# NRF24L01P.net
KiCad netlist of a schematic drawn in Altium Designer
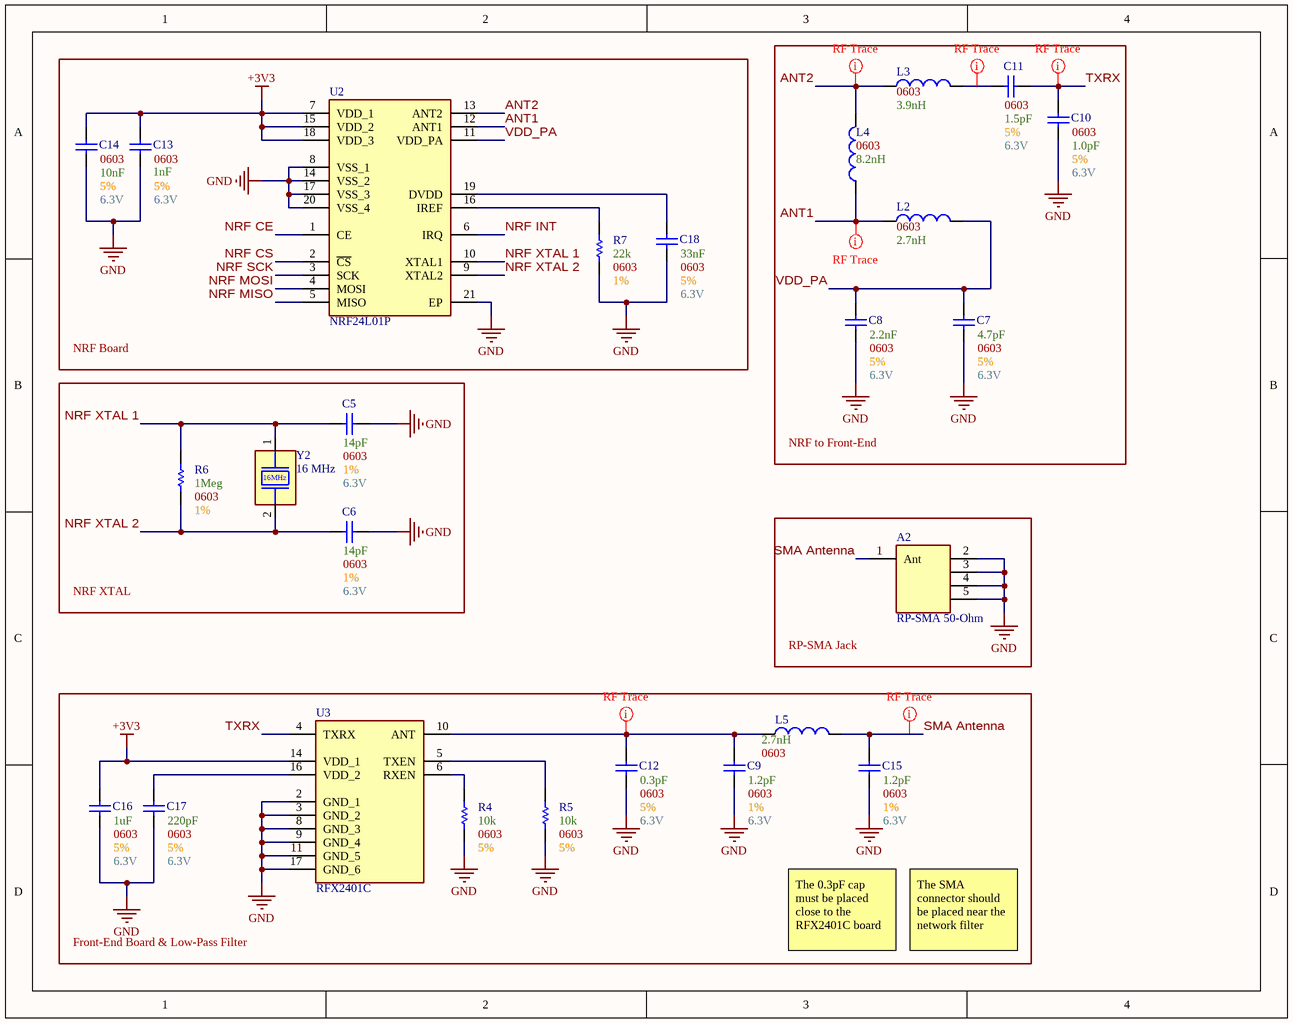
[diagram p0: NRF24L01P.SchDoc]

(export (version "E")
  (design (tool "Eeschema 10.0.6"))
  (components
    (comp (ref "A2")
      (value "RP-SMA 50-Ohm")
      (footprint "[SMA] RP-SMA 90deg Jack")
      (description "PCB.RPSMAFRA.HT")
      (libsource (lib "RADM Connectors") (part "[SMA] RP-SMA 90deg Jack"))
    )
    (comp (ref "C5")
      (value "SMD Nonpolarized")
      (footprint "[Cap] SMD 0603")
      (fields
        (field (name "TOLERANCE") "1%")
        (field (name "SIZE PACKAGE") "0603")
        (field (name "CAPACITANCE") "14pF")
        (field (name "VOLTAGE") "6.3V")
      )
      (libsource (lib "RADM Components") (part "[Cap] SMD Nonpolarized"))
    )
    (comp (ref "C6")
      (value "SMD Nonpolarized")
      (footprint "[Cap] SMD 0603")
      (fields
        (field (name "TOLERANCE") "1%")
        (field (name "SIZE PACKAGE") "0603")
        (field (name "CAPACITANCE") "14pF")
        (field (name "VOLTAGE") "6.3V")
      )
      (libsource (lib "RADM Components") (part "[Cap] SMD Nonpolarized"))
    )
    (comp (ref "C7")
      (value "SMD Nonpolarized")
      (footprint "[Cap] SMD 0603")
      (fields
        (field (name "TOLERANCE") "5%")
        (field (name "SIZE PACKAGE") "0603")
        (field (name "CAPACITANCE") "4.7pF")
        (field (name "VOLTAGE") "6.3V")
      )
      (libsource (lib "RADM Components") (part "[Cap] SMD Nonpolarized"))
    )
    (comp (ref "C8")
      (value "SMD Nonpolarized")
      (footprint "[Cap] SMD 0603")
      (fields
        (field (name "TOLERANCE") "5%")
        (field (name "SIZE PACKAGE") "0603")
        (field (name "CAPACITANCE") "2.2nF")
        (field (name "VOLTAGE") "6.3V")
      )
      (libsource (lib "RADM Components") (part "[Cap] SMD Nonpolarized"))
    )
    (comp (ref "C9")
      (value "SMD Nonpolarized")
      (footprint "[Cap] SMD 0603")
      (fields
        (field (name "VOLTAGE") "6.3V")
        (field (name "TOLERANCE") "1%")
        (field (name "SIZE PACKAGE") "0603")
        (field (name "CAPACITANCE") "1.2pF")
      )
      (libsource (lib "RADM Components") (part "[Cap] SMD Nonpolarized"))
    )
    (comp (ref "C10")
      (value "SMD Nonpolarized")
      (footprint "[Cap] SMD 0603")
      (fields
        (field (name "TOLERANCE") "5%")
        (field (name "SIZE PACKAGE") "0603")
        (field (name "CAPACITANCE") "1.0pF")
        (field (name "VOLTAGE") "6.3V")
      )
      (libsource (lib "RADM Components") (part "[Cap] SMD Nonpolarized"))
    )
    (comp (ref "C11")
      (value "SMD Nonpolarized")
      (footprint "[Cap] SMD 0603")
      (fields
        (field (name "TOLERANCE") "5%")
        (field (name "SIZE PACKAGE") "0603")
        (field (name "CAPACITANCE") "1.5pF")
        (field (name "VOLTAGE") "6.3V")
      )
      (libsource (lib "RADM Components") (part "[Cap] SMD Nonpolarized"))
    )
    (comp (ref "C12")
      (value "SMD Nonpolarized")
      (footprint "[Cap] SMD 0603")
      (fields
        (field (name "TOLERANCE") "5%")
        (field (name "SIZE PACKAGE") "0603")
        (field (name "CAPACITANCE") "0.3pF")
        (field (name "VOLTAGE") "6.3V")
      )
      (libsource (lib "RADM Components") (part "[Cap] SMD Nonpolarized"))
    )
    (comp (ref "C13")
      (value "SMD Nonpolarized")
      (footprint "[Cap] SMD 0603")
      (fields
        (field (name "TOLERANCE") "5%")
        (field (name "SIZE PACKAGE") "0603")
        (field (name "CAPACITANCE") "1nF")
        (field (name "VOLTAGE") "6.3V")
      )
      (libsource (lib "RADM Components") (part "[Cap] SMD Nonpolarized"))
    )
    (comp (ref "C14")
      (value "SMD Nonpolarized")
      (footprint "[Cap] SMD 0603")
      (fields
        (field (name "TOLERANCE") "5%")
        (field (name "SIZE PACKAGE") "0603")
        (field (name "CAPACITANCE") "10nF")
        (field (name "VOLTAGE") "6.3V")
      )
      (libsource (lib "RADM Components") (part "[Cap] SMD Nonpolarized"))
    )
    (comp (ref "C15")
      (value "SMD Nonpolarized")
      (footprint "[Cap] SMD 0603")
      (fields
        (field (name "VOLTAGE") "6.3V")
        (field (name "TOLERANCE") "1%")
        (field (name "SIZE PACKAGE") "0603")
        (field (name "CAPACITANCE") "1.2pF")
      )
      (libsource (lib "RADM Components") (part "[Cap] SMD Nonpolarized"))
    )
    (comp (ref "C16")
      (value "SMD Nonpolarized")
      (footprint "[Cap] SMD 0603")
      (fields
        (field (name "TOLERANCE") "5%")
        (field (name "SIZE PACKAGE") "0603")
        (field (name "CAPACITANCE") "1uF")
        (field (name "VOLTAGE") "6.3V")
      )
      (libsource (lib "RADM Components") (part "[Cap] SMD Nonpolarized"))
    )
    (comp (ref "C17")
      (value "SMD Nonpolarized")
      (footprint "[Cap] SMD 0603")
      (fields
        (field (name "TOLERANCE") "5%")
        (field (name "SIZE PACKAGE") "0603")
        (field (name "CAPACITANCE") "220pF")
        (field (name "VOLTAGE") "6.3V")
      )
      (libsource (lib "RADM Components") (part "[Cap] SMD Nonpolarized"))
    )
    (comp (ref "C18")
      (value "SMD Nonpolarized")
      (footprint "[Cap] SMD 0603")
      (fields
        (field (name "TOLERANCE") "5%")
        (field (name "SIZE PACKAGE") "0603")
        (field (name "CAPACITANCE") "33nF")
        (field (name "VOLTAGE") "6.3V")
      )
      (libsource (lib "RADM Components") (part "[Cap] SMD Nonpolarized"))
    )
    (comp (ref "L2")
      (value "SMD Inductor")
      (footprint "[Inductor] SMD 0603")
      (fields (field (name "SIZE PACKAGE") "0603") (field (name "INDUCTANCE") "2.7nH"))
      (libsource (lib "RADM Components") (part "[Inductor] SMD Inductor"))
    )
    (comp (ref "L3")
      (value "SMD Inductor")
      (footprint "[Inductor] SMD 0603")
      (fields (field (name "SIZE PACKAGE") "0603") (field (name "INDUCTANCE") "3.9nH"))
      (libsource (lib "RADM Components") (part "[Inductor] SMD Inductor"))
    )
    (comp (ref "L4")
      (value "SMD Inductor")
      (footprint "[Inductor] SMD 0603")
      (fields (field (name "SIZE PACKAGE") "0603") (field (name "INDUCTANCE") "8.2nH"))
      (libsource (lib "RADM Components") (part "[Inductor] SMD Inductor"))
    )
    (comp (ref "L5")
      (value "SMD Inductor")
      (footprint "[Inductor] SMD 0603")
      (fields (field (name "SIZE PACKAGE") "0603") (field (name "INDUCTANCE") "2.7nH"))
      (libsource (lib "RADM Components") (part "[Inductor] SMD Inductor"))
    )
    (comp (ref "R4")
      (value "[Res] SMD Resistor")
      (footprint "[Res] SMD 0603")
      (description "Generic")
      (fields
        (field (name "TOLERANCE") "5%")
        (field (name "RESISTANCE") "10k")
        (field (name "SIZE PACKAGE") "0603")
      )
      (libsource (lib "RADM Components") (part "[Res] SMD Resistor"))
    )
    (comp (ref "R5")
      (value "[Res] SMD Resistor")
      (footprint "[Res] SMD 0603")
      (description "Generic")
      (fields
        (field (name "TOLERANCE") "5%")
        (field (name "RESISTANCE") "10k")
        (field (name "SIZE PACKAGE") "0603")
      )
      (libsource (lib "RADM Components") (part "[Res] SMD Resistor"))
    )
    (comp (ref "R6")
      (value "[Res] SMD Resistor")
      (footprint "[Res] SMD 0603")
      (description "Generic")
      (fields
        (field (name "TOLERANCE") "1%")
        (field (name "RESISTANCE") "1Meg")
        (field (name "SIZE PACKAGE") "0603")
      )
      (libsource (lib "RADM Components") (part "[Res] SMD Resistor"))
    )
    (comp (ref "R7")
      (value "[Res] SMD Resistor")
      (footprint "[Res] SMD 0603")
      (description "Generic")
      (fields
        (field (name "TOLERANCE") "1%")
        (field (name "RESISTANCE") "22k")
        (field (name "SIZE PACKAGE") "0603")
      )
      (libsource (lib "RADM Components") (part "[Res] SMD Resistor"))
    )
    (comp (ref "U2")
      (value "NRF24L01P")
      (footprint "[IC] NRF Transceiver")
      (description "NRF24L01P-R")
      (libsource (lib "RADM Components") (part "[IC] NRF Transceiver"))
    )
    (comp (ref "U3")
      (value "RFX2401C")
      (footprint "[IC] RF Front-End")
      (libsource (lib "RADM Components") (part "[IC] RF Front-End"))
    )
    (comp (ref "Y2")
      (value "16 MHz")
      (footprint "[XTAL] SMD 16MHz (2)")
      (description "ABM11-16.000MHZ-12-N1G-T")
      (libsource (lib "RADM Components") (part "[XTAL] SMD 16MHz (2)"))
    )
  )
  (nets
    (net (code "1") (name "+3V3") (class "Default")
      (node (ref "C13") (pin "2") (pinfunction "2_2") (pintype "passive"))
      (node (ref "C14") (pin "2") (pinfunction "2_2") (pintype "passive"))
      (node (ref "C16") (pin "2") (pinfunction "2_2") (pintype "passive"))
      (node (ref "U2") (pin "15") (pinfunction "VDD_2_15") (pintype "passive"))
      (node (ref "U2") (pin "18") (pinfunction "VDD_3_18") (pintype "passive"))
      (node (ref "U2") (pin "7") (pinfunction "VDD_1_7") (pintype "passive"))
      (node (ref "U3") (pin "14") (pinfunction "VDD_1_14") (pintype "passive"))
    )
    (net (code "2") (name "/ANT1") (class "Default")
      (node (ref "L2") (pin "1") (pinfunction "1_1") (pintype "passive"))
      (node (ref "L4") (pin "1") (pinfunction "1_1") (pintype "passive"))
      (node (ref "U2") (pin "12") (pinfunction "ANT1_12") (pintype "passive"))
    )
    (net (code "3") (name "/ANT2") (class "Default")
      (node (ref "L3") (pin "1") (pinfunction "1_1") (pintype "passive"))
      (node (ref "L4") (pin "2") (pinfunction "2_2") (pintype "passive"))
      (node (ref "U2") (pin "13") (pinfunction "ANT2_13") (pintype "passive"))
    )
    (net (code "4") (name "/NRF CE") (class "Default")
      (node (ref "U2") (pin "1") (pinfunction "CE_1") (pintype "passive"))
    )
    (net (code "5") (name "/NRF CS") (class "Default")
      (node (ref "U2") (pin "2") (pinfunction "CS_2") (pintype "passive"))
    )
    (net (code "6") (name "/NRF INT") (class "Default")
      (node (ref "U2") (pin "6") (pinfunction "IRQ_6") (pintype "passive"))
    )
    (net (code "7") (name "/NRF MISO") (class "Default")
      (node (ref "U2") (pin "5") (pinfunction "MISO_5") (pintype "passive"))
    )
    (net (code "8") (name "/NRF MOSI") (class "Default")
      (node (ref "U2") (pin "4") (pinfunction "MOSI_4") (pintype "passive"))
    )
    (net (code "9") (name "/NRF SCK") (class "Default")
      (node (ref "U2") (pin "3") (pinfunction "SCK_3") (pintype "passive"))
    )
    (net (code "10") (name "/NRF XTAL 1") (class "Default")
      (node (ref "C5") (pin "1") (pinfunction "1_1") (pintype "passive"))
      (node (ref "R6") (pin "1") (pinfunction "1_1") (pintype "passive"))
      (node (ref "U2") (pin "10") (pinfunction "XTAL1_10") (pintype "passive"))
      (node (ref "Y2") (pin "1") (pinfunction "XTAL1_1") (pintype "passive"))
    )
    (net (code "11") (name "/NRF XTAL 2") (class "Default")
      (node (ref "C6") (pin "1") (pinfunction "1_1") (pintype "passive"))
      (node (ref "R6") (pin "2") (pinfunction "2_2") (pintype "passive"))
      (node (ref "U2") (pin "9") (pinfunction "XTAL2_9") (pintype "passive"))
      (node (ref "Y2") (pin "2") (pinfunction "XTAL2_2") (pintype "passive"))
    )
    (net (code "12") (name "/SMA Antenna") (class "Default")
      (node (ref "A2") (pin "1") (pinfunction "Ant_1") (pintype "passive"))
      (node (ref "C15") (pin "2") (pinfunction "2_2") (pintype "passive"))
      (node (ref "L5") (pin "2") (pinfunction "2_2") (pintype "passive"))
    )
    (net (code "13") (name "/TXRX") (class "Default")
      (node (ref "C10") (pin "1") (pinfunction "1_1") (pintype "passive"))
      (node (ref "C11") (pin "1") (pinfunction "1_1") (pintype "passive"))
      (node (ref "U3") (pin "4") (pinfunction "TXRX_4") (pintype "passive"))
    )
    (net (code "14") (name "/VDD_PA") (class "Default")
      (node (ref "C7") (pin "2") (pinfunction "2_2") (pintype "passive"))
      (node (ref "C8") (pin "2") (pinfunction "2_2") (pintype "passive"))
      (node (ref "L2") (pin "2") (pinfunction "2_2") (pintype "passive"))
      (node (ref "U2") (pin "11") (pinfunction "VDD_PA_11") (pintype "passive"))
    )
    (net (code "15") (name "GND") (class "Default")
      (node (ref "A2") (pin "2") (pinfunction "2_2") (pintype "passive"))
      (node (ref "A2") (pin "3") (pinfunction "3_3") (pintype "passive"))
      (node (ref "A2") (pin "4") (pinfunction "4_4") (pintype "passive"))
      (node (ref "A2") (pin "5") (pinfunction "5_5") (pintype "passive"))
      (node (ref "C10") (pin "2") (pinfunction "2_2") (pintype "passive"))
      (node (ref "C12") (pin "1") (pinfunction "1_1") (pintype "passive"))
      (node (ref "C13") (pin "1") (pinfunction "1_1") (pintype "passive"))
      (node (ref "C14") (pin "1") (pinfunction "1_1") (pintype "passive"))
      (node (ref "C15") (pin "1") (pinfunction "1_1") (pintype "passive"))
      (node (ref "C16") (pin "1") (pinfunction "1_1") (pintype "passive"))
      (node (ref "C17") (pin "1") (pinfunction "1_1") (pintype "passive"))
      (node (ref "C18") (pin "1") (pinfunction "1_1") (pintype "passive"))
      (node (ref "C5") (pin "2") (pinfunction "2_2") (pintype "passive"))
      (node (ref "C6") (pin "2") (pinfunction "2_2") (pintype "passive"))
      (node (ref "C7") (pin "1") (pinfunction "1_1") (pintype "passive"))
      (node (ref "C8") (pin "1") (pinfunction "1_1") (pintype "passive"))
      (node (ref "C9") (pin "1") (pinfunction "1_1") (pintype "passive"))
      (node (ref "R4") (pin "1") (pinfunction "1_1") (pintype "passive"))
      (node (ref "R5") (pin "1") (pinfunction "1_1") (pintype "passive"))
      (node (ref "R7") (pin "1") (pinfunction "1_1") (pintype "passive"))
      (node (ref "U2") (pin "14") (pinfunction "VSS_2_14") (pintype "passive"))
      (node (ref "U2") (pin "17") (pinfunction "VSS_3_17") (pintype "passive"))
      (node (ref "U2") (pin "20") (pinfunction "VSS_4_20") (pintype "passive"))
      (node (ref "U2") (pin "21") (pinfunction "EP_21") (pintype "passive"))
      (node (ref "U2") (pin "8") (pinfunction "VSS_1_8") (pintype "passive"))
      (node (ref "U3") (pin "11") (pinfunction "GND_5_11") (pintype "passive"))
      (node (ref "U3") (pin "17") (pinfunction "GND_6_17") (pintype "passive"))
      (node (ref "U3") (pin "2") (pinfunction "GND_1_2") (pintype "passive"))
      (node (ref "U3") (pin "3") (pinfunction "GND_2_3") (pintype "passive"))
      (node (ref "U3") (pin "8") (pinfunction "GND_3_8") (pintype "passive"))
      (node (ref "U3") (pin "9") (pinfunction "GND_4_9") (pintype "passive"))
    )
    (net (code "16") (name "Net-(C11-Pad2)") (class "Default")
      (node (ref "C11") (pin "2") (pinfunction "2_2") (pintype "passive"))
      (node (ref "L3") (pin "2") (pinfunction "2_2") (pintype "passive"))
    )
    (net (code "17") (name "Net-(U2-DVDD)") (class "Default")
      (node (ref "C18") (pin "2") (pinfunction "2_2") (pintype "passive"))
      (node (ref "U2") (pin "19") (pinfunction "DVDD_19") (pintype "passive"))
    )
    (net (code "18") (name "Net-(U2-IREF)") (class "Default")
      (node (ref "R7") (pin "2") (pinfunction "2_2") (pintype "passive"))
      (node (ref "U2") (pin "16") (pinfunction "IREF_16") (pintype "passive"))
    )
    (net (code "19") (name "Net-(U3-ANT)") (class "Default")
      (node (ref "C12") (pin "2") (pinfunction "2_2") (pintype "passive"))
      (node (ref "C9") (pin "2") (pinfunction "2_2") (pintype "passive"))
      (node (ref "L5") (pin "1") (pinfunction "1_1") (pintype "passive"))
      (node (ref "U3") (pin "10") (pinfunction "ANT_10") (pintype "passive"))
    )
    (net (code "20") (name "Net-(U3-RXEN)") (class "Default")
      (node (ref "R4") (pin "2") (pinfunction "2_2") (pintype "passive"))
      (node (ref "U3") (pin "6") (pinfunction "RXEN_6") (pintype "passive"))
    )
    (net (code "21") (name "Net-(U3-TXEN)") (class "Default")
      (node (ref "R5") (pin "2") (pinfunction "2_2") (pintype "passive"))
      (node (ref "U3") (pin "5") (pinfunction "TXEN_5") (pintype "passive"))
    )
    (net (code "22") (name "Net-(U3-VDD_2)") (class "Default")
      (node (ref "C17") (pin "2") (pinfunction "2_2") (pintype "passive"))
      (node (ref "U3") (pin "16") (pinfunction "VDD_2_16") (pintype "passive"))
    )
  )
)
